# 5V0_Buck.net
KiCad netlist of a schematic drawn in Altium Designer
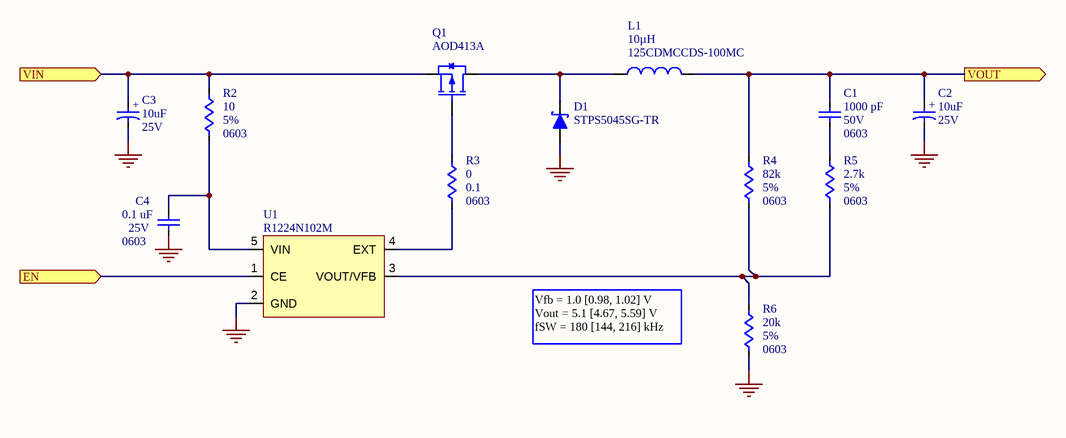
[diagram p0: 5V0_Buck.SchDoc]

(export (version "E")
  (design (tool "Eeschema 10.0.6"))
  (components
    (comp (ref "C1")
      (value "1000 pF")
      (footprint "CAPC1608X09N")
      (description "CAP CER 1000PF 50V X7R 0603")
      (fields
        (field (name "TOLERANCE") "10%")
        (field (name "VOLTAGE-RATED") "50V")
        (field (name "PACKAGE / CASE") "0603")
        (field (name "Comment") "CAP")
      )
      (libsource (lib "capacitors") (part "CAP"))
    )
    (comp (ref "C2")
      (value "10uF")
      (footprint "CAP_TH_5X12_L5")
      (description "CAP ALUM 47UF 20% 25V RADIAL")
      (fields
        (field (name "TOLERANCE") "20%")
        (field (name "VOLTAGE-RATED") "25V")
        (field (name "Comment") "CAP-POL")
      )
      (libsource (lib "capacitors") (part "CAP-POL"))
    )
    (comp (ref "C3")
      (value "10uF")
      (footprint "CAP_TH_5X12_L5")
      (description "CAP ALUM 10UF 20% 25V RADIAL")
      (fields
        (field (name "TOLERANCE") "20%")
        (field (name "VOLTAGE-RATED") "25V")
        (field (name "Comment") "CAP-POL")
      )
      (libsource (lib "capacitors") (part "CAP-POL"))
    )
    (comp (ref "C4")
      (value "0.1 uF")
      (footprint "CAPC1608X09N")
      (description "CAP CER 0.1UF 25V X5R 0603")
      (fields
        (field (name "TOLERANCE") "20%")
        (field (name "VOLTAGE-RATED") "25V")
        (field (name "PACKAGE / CASE") "0603")
        (field (name "Comment") "CAP")
      )
      (libsource (lib "capacitors") (part "CAP"))
    )
    (comp (ref "D1")
      (value "DIO-Schottky_STPS8L30B-TR")
      (footprint "DPAK254P1540X460-3N_STPS5045SG-TR")
      (description "DIODE SCHOTTKY 45V 50A D2PAK")
      (fields (field (name "MANUFACTURER PART NUMBER 1") "STPS5045SG-TR"))
      (libsource (lib "discretes") (part "DIO-Schottky_STPS8L30B-TR"))
    )
    (comp (ref "L1")
      (value "INDUCTOR")
      (footprint "125CDMCCDS-100MC")
      (description "FIXED IND 10UH 9A 22 MOHM SMD")
      (fields
        (field (name "INDUCTANCE") "10µH")
        (field (name "TOLERANCE") "±20%")
        (field (name "MANUFACTURER PART NUMBER 1") "125CDMCCDS-100MC")
      )
      (libsource (lib "magnetics") (part "INDUCTOR"))
    )
    (comp (ref "Q1")
      (value "PFET_SOT323")
      (footprint "DPAK228P991X238-3N_AOD413A")
      (description "MOSFET P-CH 40V 12A TO252")
      (fields (field (name "MANUFACTURER PART NUMBER 1") "AOD413A"))
      (libsource (lib "discretes") (part "PFET_SOT323"))
    )
    (comp (ref "R2")
      (value "10")
      (footprint "RESC1508X09N")
      (description "RES 10 OHM 5% 0603")
      (fields (field (name "TOLERANCE") "5%") (field (name "PACKAGE") "0603") (field (name "Comment") "RES"))
      (libsource (lib "resistors") (part "RES"))
    )
    (comp (ref "R3")
      (value "0")
      (footprint "RESC1508X09N")
      (description "RES 0 OHM JUMPER 1/10W 0603")
      (fields
        (field (name "POWER RATING") "0.1")
        (field (name "PACKAGE") "0603")
        (field (name "Comment") "RES")
      )
      (libsource (lib "resistors") (part "RES"))
    )
    (comp (ref "R4")
      (value "82k")
      (footprint "RESC1508X09N")
      (description "RES 82K OHM 5% 0603")
      (fields (field (name "TOLERANCE") "5%") (field (name "PACKAGE") "0603") (field (name "Comment") "RES"))
      (libsource (lib "resistors") (part "RES"))
    )
    (comp (ref "R5")
      (value "2.7k")
      (footprint "RESC1508X09N")
      (description "RES 2.7K OHM 5% 0603")
      (fields (field (name "TOLERANCE") "5%") (field (name "PACKAGE") "0603") (field (name "Comment") "RES"))
      (libsource (lib "resistors") (part "RES"))
    )
    (comp (ref "R6")
      (value "20k")
      (footprint "RESC1508X09N")
      (description "RES 20K OHM 5% 0603")
      (fields (field (name "TOLERANCE") "5%") (field (name "PACKAGE") "0603") (field (name "Comment") "RES"))
      (libsource (lib "resistors") (part "RES"))
    )
    (comp (ref "U1")
      (value "R1224N102M")
      (footprint "SOT95P280X120-5N_R1224N102M")
      (description "PWM/VFM STEP-DOWN DCDC CONTROLLE")
      (libsource (lib "ics") (part "R1224N102M"))
    )
  )
  (nets
    (net (code "1") (name "/EN") (class "Default")
      (node (ref "U1") (pin "1") (pinfunction "CE_1") (pintype "passive"))
    )
    (net (code "2") (name "/VIN") (class "Default")
      (node (ref "C3") (pin "1") (pinfunction "1_1") (pintype "passive"))
      (node (ref "Q1") (pin "S") (pinfunction "S_S") (pintype "passive"))
      (node (ref "R2") (pin "2") (pinfunction "2_2") (pintype "passive"))
    )
    (net (code "3") (name "/VOUT") (class "Default")
      (node (ref "C1") (pin "1") (pinfunction "1_1") (pintype "passive"))
      (node (ref "C2") (pin "1") (pinfunction "1_1") (pintype "passive"))
      (node (ref "L1") (pin "2") (pinfunction "2_2") (pintype "passive"))
      (node (ref "R4") (pin "2") (pinfunction "2_2") (pintype "passive"))
    )
    (net (code "4") (name "GND") (class "Default")
      (node (ref "C2") (pin "2") (pinfunction "2_2") (pintype "passive"))
      (node (ref "C3") (pin "2") (pinfunction "2_2") (pintype "passive"))
      (node (ref "C4") (pin "2") (pinfunction "2_2") (pintype "passive"))
      (node (ref "D1") (pin "A") (pinfunction "A_A") (pintype "passive"))
      (node (ref "R6") (pin "1") (pinfunction "1_1") (pintype "passive"))
      (node (ref "U1") (pin "2") (pinfunction "GND_2") (pintype "passive"))
    )
    (net (code "5") (name "Net-(C1-Pad2)") (class "Default")
      (node (ref "C1") (pin "2") (pinfunction "2_2") (pintype "passive"))
      (node (ref "R5") (pin "1") (pinfunction "1_1") (pintype "passive"))
    )
    (net (code "6") (name "Net-(D1-PadK)") (class "Default")
      (node (ref "D1") (pin "K") (pinfunction "K_K") (pintype "passive"))
      (node (ref "L1") (pin "1") (pinfunction "1_1") (pintype "passive"))
      (node (ref "Q1") (pin "D") (pinfunction "D_D") (pintype "passive"))
    )
    (net (code "7") (name "Net-(Q1-PadG)") (class "Default")
      (node (ref "Q1") (pin "G") (pinfunction "G_G") (pintype "passive"))
      (node (ref "R3") (pin "2") (pinfunction "2_2") (pintype "passive"))
    )
    (net (code "8") (name "Net-(U1-EXT)") (class "Default")
      (node (ref "R3") (pin "1") (pinfunction "1_1") (pintype "passive"))
      (node (ref "U1") (pin "4") (pinfunction "EXT_4") (pintype "passive"))
    )
    (net (code "9") (name "Net-(U1-VIN)") (class "Default")
      (node (ref "C4") (pin "1") (pinfunction "1_1") (pintype "passive"))
      (node (ref "R2") (pin "1") (pinfunction "1_1") (pintype "passive"))
      (node (ref "U1") (pin "5") (pinfunction "VIN_5") (pintype "passive"))
    )
    (net (code "10") (name "Net-(U1-VOUT{slash}VFB)") (class "Default")
      (node (ref "R4") (pin "1") (pinfunction "1_1") (pintype "passive"))
      (node (ref "R5") (pin "2") (pinfunction "2_2") (pintype "passive"))
      (node (ref "R6") (pin "2") (pinfunction "2_2") (pintype "passive"))
      (node (ref "U1") (pin "3") (pinfunction "VOUT/VFB_3") (pintype "passive"))
    )
    (net (code "11") (name "unconnected-(D1-PadNC)") (class "Default")
      (node (ref "D1") (pin "NC") (pinfunction "NC_NC") (pintype "passive"))
    )
  )
)
